# BTS.net
KiCad netlist of a schematic drawn in EAGLE
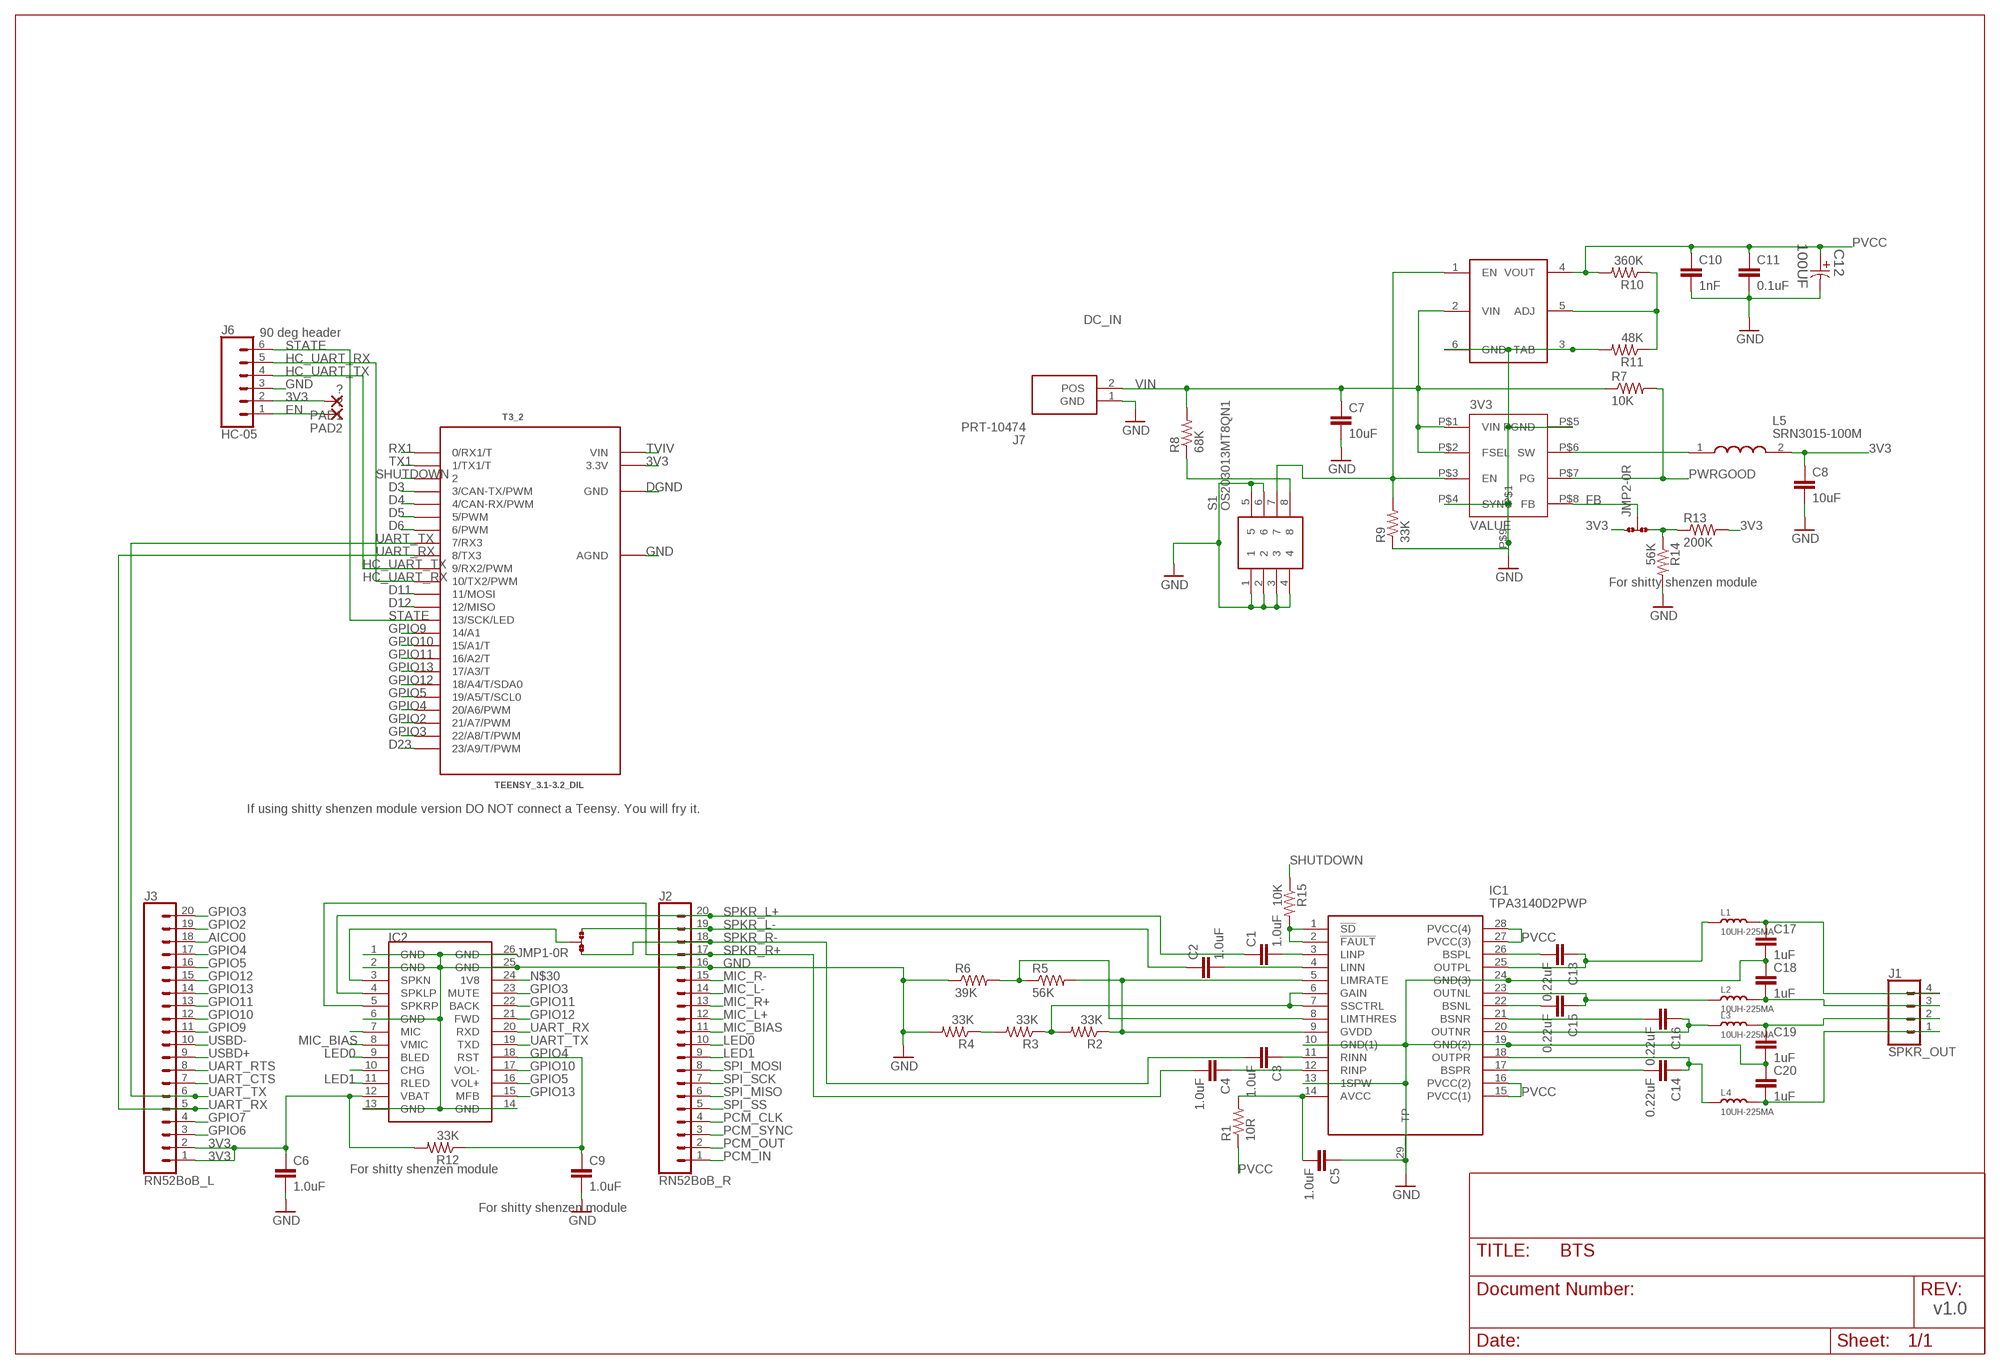
[diagram p0: schematic, sheet 1]

(export (version "E")
  (design (tool "Eeschema 10.0.6"))
  (components
    (comp (ref "3V3")
      (value "ADP2370")
      (footprint "eagle-import:3MM_LFCSP_QFN")
      (libsource (lib "eagle-import") (part "ADP2370"))
    )
    (comp (ref "C1")
      (value "1.0uF")
      (footprint "eagle-import:0603")
      (libsource (lib "eagle-import") (part "1.0UF-0603-16V-10%"))
    )
    (comp (ref "C2")
      (value "1.0uF")
      (footprint "eagle-import:0603")
      (libsource (lib "eagle-import") (part "1.0UF-0603-16V-10%"))
    )
    (comp (ref "C3")
      (value "1.0uF")
      (footprint "eagle-import:0603")
      (libsource (lib "eagle-import") (part "1.0UF-0603-16V-10%"))
    )
    (comp (ref "C4")
      (value "1.0uF")
      (footprint "eagle-import:0603")
      (libsource (lib "eagle-import") (part "1.0UF-0603-16V-10%"))
    )
    (comp (ref "C5")
      (value "1.0uF")
      (footprint "eagle-import:0603")
      (libsource (lib "eagle-import") (part "1.0UF-0603-16V-10%"))
    )
    (comp (ref "C6")
      (value "1.0uF")
      (footprint "eagle-import:0603")
      (libsource (lib "eagle-import") (part "1.0UF-0603-16V-10%"))
    )
    (comp (ref "C7")
      (value "10uF")
      (footprint "eagle-import:C3216")
      (fields (field (name "SPICEPREFIX") "10uF"))
      (libsource (lib "eagle-import") (part "C-EUC3216"))
    )
    (comp (ref "C8")
      (value "10uF")
      (footprint "eagle-import:C3216")
      (libsource (lib "eagle-import") (part "C-EUC3216"))
    )
    (comp (ref "C9")
      (value "1.0uF")
      (footprint "eagle-import:0603")
      (libsource (lib "eagle-import") (part "1.0UF-0603-16V-10%"))
    )
    (comp (ref "C10")
      (value "1nF")
      (footprint "eagle-import:0603")
      (libsource (lib "eagle-import") (part "1.0NF/1000PF-0603-50V-10%"))
    )
    (comp (ref "C11")
      (value "0.1uF")
      (footprint "eagle-import:0603")
      (libsource (lib "eagle-import") (part "0.1UF-0603-25V-(+80/-20%)"))
    )
    (comp (ref "C12")
      (value "100UF")
      (footprint "eagle-import:CAPAE660X610N")
      (fields (field (name "MPN") "EEE-FK1C101P") (field (name "TOLERANCE") "±20 %"))
      (libsource (lib "eagle-import") (part "EEE--CASE-DFK1C101P"))
    )
    (comp (ref "C13")
      (value "0.22uF")
      (footprint "eagle-import:0603")
      (libsource (lib "eagle-import") (part "0.22UF-0603-50V-(-20/+80%)"))
    )
    (comp (ref "C14")
      (value "0.22uF")
      (footprint "eagle-import:0603")
      (libsource (lib "eagle-import") (part "0.22UF-0603-50V-(-20/+80%)"))
    )
    (comp (ref "C15")
      (value "0.22uF")
      (footprint "eagle-import:0603")
      (libsource (lib "eagle-import") (part "0.22UF-0603-50V-(-20/+80%)"))
    )
    (comp (ref "C16")
      (value "0.22uF")
      (footprint "eagle-import:0603")
      (libsource (lib "eagle-import") (part "0.22UF-0603-50V-(-20/+80%)"))
    )
    (comp (ref "C17")
      (value "1uF")
      (footprint "eagle-import:0603")
      (libsource (lib "eagle-import") (part "1.0NF/1000PF-0603-50V-10%"))
    )
    (comp (ref "C18")
      (value "1uF")
      (footprint "eagle-import:0603")
      (libsource (lib "eagle-import") (part "1.0NF/1000PF-0603-50V-10%"))
    )
    (comp (ref "C19")
      (value "1uF")
      (footprint "eagle-import:0603")
      (libsource (lib "eagle-import") (part "1.0NF/1000PF-0603-50V-10%"))
    )
    (comp (ref "C20")
      (value "1uF")
      (footprint "eagle-import:0603")
      (libsource (lib "eagle-import") (part "1.0NF/1000PF-0603-50V-10%"))
    )
    (comp (ref "IC1")
      (value "TPA3140D2PWP")
      (footprint "eagle-import:SOP65P640X120-29N")
      (libsource (lib "eagle-import") (part "TPA3140D2PWP"))
    )
    (comp (ref "IC2")
      (value "BLK-MD-SPK-B")
      (footprint "eagle-import:BLK-MD-SPK-B")
      (libsource (lib "eagle-import") (part "BLK-MD-SPK-B"))
    )
    (comp (ref "J1")
      (value "SPKR_OUT")
      (footprint "eagle-import:SCREWTERMINAL-3.5MM-4")
      (libsource (lib "eagle-import") (part "CONN_04SCREW"))
    )
    (comp (ref "J2")
      (value "RN52BoB_R")
      (footprint "eagle-import:1X20")
      (libsource (lib "eagle-import") (part "CONN_20"))
    )
    (comp (ref "J3")
      (value "RN52BoB_L")
      (footprint "eagle-import:1X20")
      (libsource (lib "eagle-import") (part "CONN_20"))
    )
    (comp (ref "J6")
      (value "HC-05")
      (footprint "eagle-import:1X06")
      (libsource (lib "eagle-import") (part "CONN_06SILK_FEMALE_PTH"))
    )
    (comp (ref "J7")
      (value "PRT-10474")
      (footprint "eagle-import:SHDR2W320P716_1X2_1574X813X158")
      (libsource (lib "eagle-import") (part "PRT-10474"))
    )
    (comp (ref "JMP1")
      (value "0R-JUMPA")
      (footprint "eagle-import:A0R-JMP")
      (libsource (lib "eagle-import") (part "0R-JUMPA"))
    )
    (comp (ref "JMP2")
      (value "0R-JUMPA")
      (footprint "eagle-import:A0R-JMP")
      (libsource (lib "eagle-import") (part "0R-JUMPA"))
    )
    (comp (ref "L1")
      (value "10UH-225MA")
      (footprint "eagle-import:L0806")
      (fields (field (name "MPN") "LQH2MCN100K02L"))
      (libsource (lib "eagle-import") (part "SMD-INDUCTOR-10UH-225MA-10%(0806)"))
    )
    (comp (ref "L2")
      (value "10UH-225MA")
      (footprint "eagle-import:L0806")
      (fields (field (name "MPN") "LQH2MCN100K02L"))
      (libsource (lib "eagle-import") (part "SMD-INDUCTOR-10UH-225MA-10%(0806)"))
    )
    (comp (ref "L3")
      (value "10UH-225MA")
      (footprint "eagle-import:L0806")
      (fields (field (name "MPN") "LQH2MCN100K02L"))
      (libsource (lib "eagle-import") (part "SMD-INDUCTOR-10UH-225MA-10%(0806)"))
    )
    (comp (ref "L4")
      (value "10UH-225MA")
      (footprint "eagle-import:L0806")
      (fields (field (name "MPN") "LQH2MCN100K02L"))
      (libsource (lib "eagle-import") (part "SMD-INDUCTOR-10UH-225MA-10%(0806)"))
    )
    (comp (ref "L5")
      (value "SRN3015-100M")
      (footprint "eagle-import:SRN3015")
      (fields (field (name "RS_PART_NUMBER") "7435071"))
      (libsource (lib "eagle-import") (part "SRN3015-100M"))
    )
    (comp (ref "PAD1")
      (value "?")
      (footprint "eagle-import:SMD1,27-2,54")
      (libsource (lib "eagle-import") (part "SMD2"))
    )
    (comp (ref "PAD2")
      (value "?")
      (footprint "eagle-import:SMD1,27-2,54")
      (libsource (lib "eagle-import") (part "SMD2"))
    )
    (comp (ref "R1")
      (value "10R")
      (footprint "eagle-import:R0603")
      (fields (field (name "RESISTANCE") "10R"))
      (libsource (lib "eagle-import") (part "R-US_R0603"))
    )
    (comp (ref "R2")
      (value "33K")
      (footprint "eagle-import:R0603")
      (fields (field (name "RESISTANCE") "33K"))
      (libsource (lib "eagle-import") (part "R-US_R0603"))
    )
    (comp (ref "R3")
      (value "33K")
      (footprint "eagle-import:R0603")
      (fields (field (name "RESISTANCE") "33K"))
      (libsource (lib "eagle-import") (part "R-US_R0603"))
    )
    (comp (ref "R4")
      (value "33K")
      (footprint "eagle-import:R0603")
      (fields (field (name "RESISTANCE") "33K"))
      (libsource (lib "eagle-import") (part "R-US_R0603"))
    )
    (comp (ref "R5")
      (value "56K")
      (footprint "eagle-import:R0603")
      (fields (field (name "RESISTANCE") "56K"))
      (libsource (lib "eagle-import") (part "R-US_R0603"))
    )
    (comp (ref "R6")
      (value "39K")
      (footprint "eagle-import:R0603")
      (fields (field (name "RESISTANCE") "39K"))
      (libsource (lib "eagle-import") (part "R-US_R0603"))
    )
    (comp (ref "R7")
      (value "10K")
      (footprint "eagle-import:R0603")
      (fields (field (name "RESISTANCE") "10K"))
      (libsource (lib "eagle-import") (part "R-US_R0603"))
    )
    (comp (ref "R8")
      (value "68K")
      (footprint "eagle-import:R0603")
      (fields (field (name "RESISTANCE") "68K"))
      (libsource (lib "eagle-import") (part "R-US_R0603"))
    )
    (comp (ref "R9")
      (value "33K")
      (footprint "eagle-import:R0603")
      (fields (field (name "RESISTANCE") "33K"))
      (libsource (lib "eagle-import") (part "R-US_R0603"))
    )
    (comp (ref "R10")
      (value "360K")
      (footprint "eagle-import:R0603")
      (fields (field (name "RESISTANCE") "10K"))
      (libsource (lib "eagle-import") (part "R-US_R0603"))
    )
    (comp (ref "R11")
      (value "48K")
      (footprint "eagle-import:R0603")
      (fields (field (name "RESISTANCE") "10K"))
      (libsource (lib "eagle-import") (part "R-US_R0603"))
    )
    (comp (ref "R12")
      (value "33K")
      (footprint "eagle-import:R0603")
      (fields (field (name "RESISTANCE") "33K"))
      (libsource (lib "eagle-import") (part "R-US_R0603"))
    )
    (comp (ref "R13")
      (value "200K")
      (footprint "eagle-import:R0603")
      (fields (field (name "RESISTANCE") "10K"))
      (libsource (lib "eagle-import") (part "R-US_R0603"))
    )
    (comp (ref "R14")
      (value "56K")
      (footprint "eagle-import:R0603")
      (fields (field (name "RESISTANCE") "10K"))
      (libsource (lib "eagle-import") (part "R-US_R0603"))
    )
    (comp (ref "R15")
      (value "10K")
      (footprint "eagle-import:R0603")
      (fields (field (name "RESISTANCE") "33K"))
      (libsource (lib "eagle-import") (part "R-US_R0603"))
    )
    (comp (ref "S1")
      (value "OS203013MT8QN1")
      (footprint "eagle-import:OS203013MT8QN1")
      (libsource (lib "eagle-import") (part "OS203013MT8QN1"))
    )
    (comp (ref "T3_2")
      (value "TEENSY_3.1-3.2_DIL")
      (footprint "eagle-import:TEENSY_3.0-3.2&LC_DIL")
      (libsource (lib "eagle-import") (part "TEENSY_3.1-3.2_DIL"))
    )
    (comp (ref "U$2")
      (value "NCP59302")
      (footprint "eagle-import:D2PAK-5")
      (libsource (lib "eagle-import") (part "NCP59302"))
    )
  )
  (nets
    (net (code "1") (name "/3V3") (class "Default")
      (node (ref "C6") (pin "1") (pinfunction "1_1") (pintype "passive"))
      (node (ref "C8") (pin "1") (pinfunction "1_1") (pintype "passive"))
      (node (ref "IC2") (pin "12") (pinfunction "VBAT_12") (pintype "bidirectional"))
      (node (ref "J3") (pin "1") (pinfunction "1_1") (pintype "passive"))
      (node (ref "J3") (pin "2") (pinfunction "2_2") (pintype "passive"))
      (node (ref "J6") (pin "2") (pinfunction "2_2") (pintype "passive"))
      (node (ref "JMP2") (pin "1") (pinfunction "1_1") (pintype "passive"))
      (node (ref "L5") (pin "2") (pinfunction "2_2") (pintype "input"))
      (node (ref "PAD1") (pin "1") (pinfunction "P_1") (pintype "passive"))
      (node (ref "R12") (pin "2") (pinfunction "2_2") (pintype "passive"))
      (node (ref "R13") (pin "2") (pinfunction "2_2") (pintype "passive"))
      (node (ref "T3_2") (pin "3.3V") (pinfunction "3.3V_3.3V") (pintype "power_in"))
    )
    (net (code "2") (name "/AICO0") (class "Default")
      (node (ref "J3") (pin "18") (pinfunction "18_18") (pintype "passive"))
    )
    (net (code "3") (name "/D3") (class "Default")
      (node (ref "T3_2") (pin "3") (pinfunction "3/CAN-TX/PWM_3") (pintype "bidirectional"))
    )
    (net (code "4") (name "/D4") (class "Default")
      (node (ref "T3_2") (pin "4") (pinfunction "4/CAN-RX/PWM_4") (pintype "bidirectional"))
    )
    (net (code "5") (name "/D5") (class "Default")
      (node (ref "T3_2") (pin "5") (pinfunction "5/PWM_5") (pintype "bidirectional"))
    )
    (net (code "6") (name "/D6") (class "Default")
      (node (ref "T3_2") (pin "6") (pinfunction "6/PWM_6") (pintype "bidirectional"))
    )
    (net (code "7") (name "/D11") (class "Default")
      (node (ref "T3_2") (pin "11") (pinfunction "11/MOSI_11") (pintype "bidirectional"))
    )
    (net (code "8") (name "/D12") (class "Default")
      (node (ref "T3_2") (pin "12") (pinfunction "12/MISO_12") (pintype "bidirectional"))
    )
    (net (code "9") (name "/D23") (class "Default")
      (node (ref "T3_2") (pin "23/A9") (pinfunction "23/A9/T/PWM_23/A9") (pintype "bidirectional"))
    )
    (net (code "10") (name "/DGND") (class "Default")
      (node (ref "T3_2") (pin "GND") (pinfunction "GND_GND") (pintype "power_in"))
    )
    (net (code "11") (name "/EN") (class "Default")
      (node (ref "J6") (pin "1") (pinfunction "1_1") (pintype "passive"))
      (node (ref "PAD2") (pin "1") (pinfunction "P_1") (pintype "passive"))
    )
    (net (code "12") (name "/FB") (class "Default")
      (node (ref "3V3") (pin "P$8") (pinfunction "FB_P$8") (pintype "bidirectional"))
      (node (ref "JMP2") (pin "2") (pinfunction "2_2") (pintype "passive"))
    )
    (net (code "13") (name "/GPIO2") (class "Default")
      (node (ref "J3") (pin "19") (pinfunction "19_19") (pintype "passive"))
      (node (ref "T3_2") (pin "21/A7") (pinfunction "21/A7/PWM_21/A7") (pintype "bidirectional"))
    )
    (net (code "14") (name "/GPIO3") (class "Default")
      (node (ref "IC2") (pin "23") (pinfunction "MUTE_23") (pintype "bidirectional"))
      (node (ref "J3") (pin "20") (pinfunction "20_20") (pintype "passive"))
      (node (ref "T3_2") (pin "22/A8") (pinfunction "22/A8/T/PWM_22/A8") (pintype "bidirectional"))
    )
    (net (code "15") (name "/GPIO4") (class "Default")
      (node (ref "C9") (pin "1") (pinfunction "1_1") (pintype "passive"))
      (node (ref "IC2") (pin "18") (pinfunction "RST_18") (pintype "bidirectional"))
      (node (ref "J3") (pin "17") (pinfunction "17_17") (pintype "passive"))
      (node (ref "R12") (pin "1") (pinfunction "1_1") (pintype "passive"))
      (node (ref "T3_2") (pin "20/A6") (pinfunction "20/A6/PWM_20/A6") (pintype "bidirectional"))
    )
    (net (code "16") (name "/GPIO5") (class "Default")
      (node (ref "IC2") (pin "16") (pinfunction "VOL+_16") (pintype "bidirectional"))
      (node (ref "J3") (pin "16") (pinfunction "16_16") (pintype "passive"))
      (node (ref "T3_2") (pin "19/A5") (pinfunction "19/A5/T/SCL0_19/A5") (pintype "bidirectional"))
    )
    (net (code "17") (name "/GPIO6") (class "Default")
      (node (ref "J3") (pin "3") (pinfunction "3_3") (pintype "passive"))
    )
    (net (code "18") (name "/GPIO7") (class "Default")
      (node (ref "J3") (pin "4") (pinfunction "4_4") (pintype "passive"))
    )
    (net (code "19") (name "/GPIO9") (class "Default")
      (node (ref "J3") (pin "11") (pinfunction "11_11") (pintype "passive"))
      (node (ref "T3_2") (pin "14/A0") (pinfunction "14/A1_14/A0") (pintype "bidirectional"))
    )
    (net (code "20") (name "/GPIO10") (class "Default")
      (node (ref "IC2") (pin "17") (pinfunction "VOL-_17") (pintype "bidirectional"))
      (node (ref "J3") (pin "12") (pinfunction "12_12") (pintype "passive"))
      (node (ref "T3_2") (pin "15/A1") (pinfunction "15/A1/T_15/A1") (pintype "bidirectional"))
    )
    (net (code "21") (name "/GPIO11") (class "Default")
      (node (ref "IC2") (pin "22") (pinfunction "BACK_22") (pintype "bidirectional"))
      (node (ref "J3") (pin "13") (pinfunction "13_13") (pintype "passive"))
      (node (ref "T3_2") (pin "16/A2") (pinfunction "16/A2/T_16/A2") (pintype "bidirectional"))
    )
    (net (code "22") (name "/GPIO12") (class "Default")
      (node (ref "IC2") (pin "21") (pinfunction "FWD_21") (pintype "bidirectional"))
      (node (ref "J3") (pin "15") (pinfunction "15_15") (pintype "passive"))
      (node (ref "T3_2") (pin "18/A4") (pinfunction "18/A4/T/SDA0_18/A4") (pintype "bidirectional"))
    )
    (net (code "23") (name "/GPIO13") (class "Default")
      (node (ref "IC2") (pin "15") (pinfunction "MFB_15") (pintype "bidirectional"))
      (node (ref "J3") (pin "14") (pinfunction "14_14") (pintype "passive"))
      (node (ref "T3_2") (pin "17/A3") (pinfunction "17/A3/T_17/A3") (pintype "bidirectional"))
    )
    (net (code "24") (name "/HC_UART_RX") (class "Default")
      (node (ref "J6") (pin "5") (pinfunction "5_5") (pintype "passive"))
      (node (ref "T3_2") (pin "10") (pinfunction "10/TX2/PWM_10") (pintype "bidirectional"))
    )
    (net (code "25") (name "/HC_UART_TX") (class "Default")
      (node (ref "J6") (pin "4") (pinfunction "4_4") (pintype "passive"))
      (node (ref "T3_2") (pin "9") (pinfunction "9/RX2/PWM_9") (pintype "bidirectional"))
    )
    (net (code "26") (name "/LED0") (class "Default")
      (node (ref "IC2") (pin "9") (pinfunction "BLED_9") (pintype "bidirectional"))
      (node (ref "J2") (pin "10") (pinfunction "10_10") (pintype "passive"))
    )
    (net (code "27") (name "/LED1") (class "Default")
      (node (ref "IC2") (pin "11") (pinfunction "RLED_11") (pintype "bidirectional"))
      (node (ref "J2") (pin "9") (pinfunction "9_9") (pintype "passive"))
    )
    (net (code "28") (name "/MIC_BIAS") (class "Default")
      (node (ref "IC2") (pin "8") (pinfunction "VMIC_8") (pintype "bidirectional"))
      (node (ref "J2") (pin "11") (pinfunction "11_11") (pintype "passive"))
    )
    (net (code "29") (name "/MIC_L+") (class "Default")
      (node (ref "J2") (pin "12") (pinfunction "12_12") (pintype "passive"))
    )
    (net (code "30") (name "/MIC_L-") (class "Default")
      (node (ref "J2") (pin "14") (pinfunction "14_14") (pintype "passive"))
    )
    (net (code "31") (name "/MIC_R+") (class "Default")
      (node (ref "J2") (pin "13") (pinfunction "13_13") (pintype "passive"))
    )
    (net (code "32") (name "/MIC_R-") (class "Default")
      (node (ref "J2") (pin "15") (pinfunction "15_15") (pintype "passive"))
    )
    (net (code "33") (name "/N$30") (class "Default")
      (node (ref "IC2") (pin "24") (pinfunction "1V8_24") (pintype "bidirectional"))
    )
    (net (code "34") (name "/PCM_CLK") (class "Default")
      (node (ref "J2") (pin "4") (pinfunction "4_4") (pintype "passive"))
    )
    (net (code "35") (name "/PCM_IN") (class "Default")
      (node (ref "J2") (pin "1") (pinfunction "1_1") (pintype "passive"))
    )
    (net (code "36") (name "/PCM_OUT") (class "Default")
      (node (ref "J2") (pin "2") (pinfunction "2_2") (pintype "passive"))
    )
    (net (code "37") (name "/PCM_SYNC") (class "Default")
      (node (ref "J2") (pin "3") (pinfunction "3_3") (pintype "passive"))
    )
    (net (code "38") (name "/PVCC") (class "Default")
      (node (ref "C10") (pin "1") (pinfunction "1_1") (pintype "passive"))
      (node (ref "C11") (pin "1") (pinfunction "1_1") (pintype "passive"))
      (node (ref "C12") (pin "1") (pinfunction "1_1") (pintype "passive"))
      (node (ref "IC1") (pin "15") (pinfunction "PVCC(1)_15") (pintype "input"))
      (node (ref "IC1") (pin "16") (pinfunction "PVCC(2)_16") (pintype "input"))
      (node (ref "IC1") (pin "27") (pinfunction "PVCC(3)_27") (pintype "input"))
      (node (ref "IC1") (pin "28") (pinfunction "PVCC(4)_28") (pintype "input"))
      (node (ref "R1") (pin "1") (pinfunction "1_1") (pintype "passive"))
      (node (ref "R10") (pin "2") (pinfunction "2_2") (pintype "passive"))
      (node (ref "U$2") (pin "4") (pinfunction "VOUT_4") (pintype "bidirectional"))
    )
    (net (code "39") (name "/PWRGOOD") (class "Default")
      (node (ref "3V3") (pin "P$7") (pinfunction "PG_P$7") (pintype "bidirectional"))
      (node (ref "R7") (pin "2") (pinfunction "2_2") (pintype "passive"))
    )
    (net (code "40") (name "/RX1") (class "Default")
      (node (ref "T3_2") (pin "0") (pinfunction "0/RX1/T_0") (pintype "bidirectional"))
    )
    (net (code "41") (name "/SHUTDOWN") (class "Default")
      (node (ref "R15") (pin "1") (pinfunction "1_1") (pintype "passive"))
      (node (ref "T3_2") (pin "2") (pinfunction "2_2") (pintype "bidirectional"))
    )
    (net (code "42") (name "/SPI_MISO") (class "Default")
      (node (ref "J2") (pin "6") (pinfunction "6_6") (pintype "passive"))
    )
    (net (code "43") (name "/SPI_MOSI") (class "Default")
      (node (ref "J2") (pin "8") (pinfunction "8_8") (pintype "passive"))
    )
    (net (code "44") (name "/SPI_SCK") (class "Default")
      (node (ref "J2") (pin "7") (pinfunction "7_7") (pintype "passive"))
    )
    (net (code "45") (name "/SPI_SS") (class "Default")
      (node (ref "J2") (pin "5") (pinfunction "5_5") (pintype "passive"))
    )
    (net (code "46") (name "/SPKR_L+") (class "Default")
      (node (ref "C1") (pin "1") (pinfunction "1_1") (pintype "passive"))
      (node (ref "IC2") (pin "4") (pinfunction "SPKLP_4") (pintype "bidirectional"))
      (node (ref "J2") (pin "20") (pinfunction "20_20") (pintype "passive"))
    )
    (net (code "47") (name "/SPKR_L-") (class "Default")
      (node (ref "C2") (pin "1") (pinfunction "1_1") (pintype "passive"))
      (node (ref "J2") (pin "19") (pinfunction "19_19") (pintype "passive"))
      (node (ref "JMP1") (pin "3") (pinfunction "3_3") (pintype "passive"))
    )
    (net (code "48") (name "/SPKR_R+") (class "Default")
      (node (ref "C4") (pin "2") (pinfunction "2_2") (pintype "passive"))
      (node (ref "IC2") (pin "5") (pinfunction "SPKRP_5") (pintype "bidirectional"))
      (node (ref "J2") (pin "17") (pinfunction "17_17") (pintype "passive"))
    )
    (net (code "49") (name "/SPKR_R-") (class "Default")
      (node (ref "C3") (pin "2") (pinfunction "2_2") (pintype "passive"))
      (node (ref "J2") (pin "18") (pinfunction "18_18") (pintype "passive"))
      (node (ref "JMP1") (pin "1") (pinfunction "1_1") (pintype "passive"))
    )
    (net (code "50") (name "/STATE") (class "Default")
      (node (ref "J6") (pin "6") (pinfunction "6_6") (pintype "passive"))
      (node (ref "T3_2") (pin "13") (pinfunction "13/SCK/LED_13") (pintype "bidirectional"))
    )
    (net (code "51") (name "/TVIV") (class "Default")
      (node (ref "T3_2") (pin "VIN") (pinfunction "VIN_VIN") (pintype "power_in"))
    )
    (net (code "52") (name "/TX1") (class "Default")
      (node (ref "T3_2") (pin "1") (pinfunction "1/TX1/T_1") (pintype "bidirectional"))
    )
    (net (code "53") (name "/UART_CTS") (class "Default")
      (node (ref "J3") (pin "7") (pinfunction "7_7") (pintype "passive"))
    )
    (net (code "54") (name "/UART_RTS") (class "Default")
      (node (ref "J3") (pin "8") (pinfunction "8_8") (pintype "passive"))
    )
    (net (code "55") (name "/UART_RX") (class "Default")
      (node (ref "IC2") (pin "20") (pinfunction "RXD_20") (pintype "bidirectional"))
      (node (ref "J3") (pin "5") (pinfunction "5_5") (pintype "passive"))
      (node (ref "T3_2") (pin "8") (pinfunction "8/TX3_8") (pintype "bidirectional"))
    )
    (net (code "56") (name "/UART_TX") (class "Default")
      (node (ref "IC2") (pin "19") (pinfunction "TXD_19") (pintype "bidirectional"))
      (node (ref "J3") (pin "6") (pinfunction "6_6") (pintype "passive"))
      (node (ref "T3_2") (pin "7") (pinfunction "7/RX3_7") (pintype "bidirectional"))
    )
    (net (code "57") (name "/USBD+") (class "Default")
      (node (ref "J3") (pin "9") (pinfunction "9_9") (pintype "passive"))
    )
    (net (code "58") (name "/USBD-") (class "Default")
      (node (ref "J3") (pin "10") (pinfunction "10_10") (pintype "passive"))
    )
    (net (code "59") (name "/VIN") (class "Default")
      (node (ref "3V3") (pin "P$1") (pinfunction "VIN_P$1") (pintype "bidirectional"))
      (node (ref "3V3") (pin "P$2") (pinfunction "FSEL_P$2") (pintype "bidirectional"))
      (node (ref "C7") (pin "1") (pinfunction "1_1") (pintype "passive"))
      (node (ref "J7") (pin "2") (pinfunction "POS_2") (pintype "input"))
      (node (ref "R7") (pin "1") (pinfunction "1_1") (pintype "passive"))
      (node (ref "R8") (pin "2") (pinfunction "2_2") (pintype "passive"))
      (node (ref "U$2") (pin "2") (pinfunction "VIN_2") (pintype "bidirectional"))
    )
    (net (code "60") (name "GND") (class "Default")
      (node (ref "3V3") (pin "P$4") (pinfunction "SYNC_P$4") (pintype "bidirectional"))
      (node (ref "3V3") (pin "P$5") (pinfunction "PGND_P$5") (pintype "bidirectional"))
      (node (ref "3V3") (pin "P$9") (pinfunction "P$1_P$9") (pintype "bidirectional"))
      (node (ref "C10") (pin "2") (pinfunction "2_2") (pintype "passive"))
      (node (ref "C11") (pin "2") (pinfunction "2_2") (pintype "passive"))
      (node (ref "C12") (pin "2") (pinfunction "2_2") (pintype "passive"))
      (node (ref "C17") (pin "2") (pinfunction "2_2") (pintype "passive"))
      (node (ref "C18") (pin "1") (pinfunction "1_1") (pintype "passive"))
      (node (ref "C19") (pin "2") (pinfunction "2_2") (pintype "passive"))
      (node (ref "C20") (pin "1") (pinfunction "1_1") (pintype "passive"))
      (node (ref "C5") (pin "1") (pinfunction "1_1") (pintype "passive"))
      (node (ref "C6") (pin "2") (pinfunction "2_2") (pintype "passive"))
      (node (ref "C7") (pin "2") (pinfunction "2_2") (pintype "passive"))
      (node (ref "C8") (pin "2") (pinfunction "2_2") (pintype "passive"))
      (node (ref "C9") (pin "2") (pinfunction "2_2") (pintype "passive"))
      (node (ref "IC1") (pin "10") (pinfunction "GND(1)_10") (pintype "input"))
      (node (ref "IC1") (pin "13") (pinfunction "1SPW_13") (pintype "input"))
      (node (ref "IC1") (pin "19") (pinfunction "GND(2)_19") (pintype "input"))
      (node (ref "IC1") (pin "24") (pinfunction "GND(3)_24") (pintype "input"))
      (node (ref "IC1") (pin "29") (pinfunction "TP_29") (pintype "input"))
      (node (ref "IC2") (pin "1") (pinfunction "GND_1") (pintype "bidirectional"))
      (node (ref "IC2") (pin "13") (pinfunction "GND_13") (pintype "bidirectional"))
      (node (ref "IC2") (pin "14") (pinfunction "GND_14") (pintype "bidirectional"))
      (node (ref "IC2") (pin "2") (pinfunction "GND_2") (pintype "bidirectional"))
      (node (ref "IC2") (pin "25") (pinfunction "GND_25") (pintype "bidirectional"))
      (node (ref "IC2") (pin "26") (pinfunction "GND_26") (pintype "bidirectional"))
      (node (ref "IC2") (pin "6") (pinfunction "GND_6") (pintype "bidirectional"))
      (node (ref "J2") (pin "16") (pinfunction "16_16") (pintype "passive"))
      (node (ref "J6") (pin "3") (pinfunction "3_3") (pintype "passive"))
      (node (ref "J7") (pin "1") (pinfunction "GND_1") (pintype "input"))
      (node (ref "R11") (pin "2") (pinfunction "2_2") (pintype "passive"))
      (node (ref "R14") (pin "2") (pinfunction "2_2") (pintype "passive"))
      (node (ref "R4") (pin "2") (pinfunction "2_2") (pintype "passive"))
      (node (ref "R6") (pin "1") (pinfunction "1_1") (pintype "passive"))
      (node (ref "R9") (pin "1") (pinfunction "1_1") (pintype "passive"))
      (node (ref "S1") (pin "1") (pinfunction "1_1") (pintype "input"))
      (node (ref "S1") (pin "2") (pinfunction "2_2") (pintype "input"))
      (node (ref "S1") (pin "3") (pinfunction "3_3") (pintype "input"))
      (node (ref "S1") (pin "4") (pinfunction "4_4") (pintype "input"))
      (node (ref "S1") (pin "5") (pinfunction "5_5") (pintype "input"))
      (node (ref "S1") (pin "6") (pinfunction "6_6") (pintype "input"))
      (node (ref "T3_2") (pin "AGND") (pinfunction "AGND_AGND") (pintype "power_in"))
      (node (ref "U$2") (pin "3") (pinfunction "TAB_3") (pintype "bidirectional"))
      (node (ref "U$2") (pin "6") (pinfunction "GND_6") (pintype "bidirectional"))
    )
    (net (code "61") (name "Net-(3V3-EN)") (class "Default")
      (node (ref "3V3") (pin "P$3") (pinfunction "EN_P$3") (pintype "bidirectional"))
      (node (ref "R9") (pin "2") (pinfunction "2_2") (pintype "passive"))
      (node (ref "S1") (pin "7") (pinfunction "7_7") (pintype "input"))
      (node (ref "U$2") (pin "1") (pinfunction "EN_1") (pintype "bidirectional"))
    )
    (net (code "62") (name "Net-(3V3-SW)") (class "Default")
      (node (ref "3V3") (pin "P$6") (pinfunction "SW_P$6") (pintype "bidirectional"))
      (node (ref "L5") (pin "1") (pinfunction "1_1") (pintype "input"))
    )
    (net (code "63") (name "Net-(C17-Pad1)") (class "Default")
      (node (ref "C17") (pin "1") (pinfunction "1_1") (pintype "passive"))
      (node (ref "J1") (pin "4") (pinfunction "4_4") (pintype "passive"))
      (node (ref "L1") (pin "2") (pinfunction "2_2") (pintype "passive"))
    )
    (net (code "64") (name "Net-(C18-Pad2)") (class "Default")
      (node (ref "C18") (pin "2") (pinfunction "2_2") (pintype "passive"))
      (node (ref "J1") (pin "3") (pinfunction "3_3") (pintype "passive"))
      (node (ref "L2") (pin "2") (pinfunction "2_2") (pintype "passive"))
    )
    (net (code "65") (name "Net-(C19-Pad1)") (class "Default")
      (node (ref "C19") (pin "1") (pinfunction "1_1") (pintype "passive"))
      (node (ref "J1") (pin "2") (pinfunction "2_2") (pintype "passive"))
      (node (ref "L3") (pin "2") (pinfunction "2_2") (pintype "passive"))
    )
    (net (code "66") (name "Net-(C20-Pad2)") (class "Default")
      (node (ref "C20") (pin "2") (pinfunction "2_2") (pintype "passive"))
      (node (ref "J1") (pin "1") (pinfunction "1_1") (pintype "passive"))
      (node (ref "L4") (pin "2") (pinfunction "2_2") (pintype "passive"))
    )
    (net (code "67") (name "Net-(IC1-AVCC)") (class "Default")
      (node (ref "C5") (pin "2") (pinfunction "2_2") (pintype "passive"))
      (node (ref "IC1") (pin "14") (pinfunction "AVCC_14") (pintype "input"))
      (node (ref "R1") (pin "2") (pinfunction "2_2") (pintype "passive"))
    )
    (net (code "68") (name "Net-(IC1-BSNL)") (class "Default")
      (node (ref "C15") (pin "2") (pinfunction "2_2") (pintype "passive"))
      (node (ref "IC1") (pin "22") (pinfunction "BSNL_22") (pintype "input"))
    )
    (net (code "69") (name "Net-(IC1-BSNR)") (class "Default")
      (node (ref "C16") (pin "2") (pinfunction "2_2") (pintype "passive"))
      (node (ref "IC1") (pin "21") (pinfunction "BSNR_21") (pintype "input"))
    )
    (net (code "70") (name "Net-(IC1-BSPL)") (class "Default")
      (node (ref "C13") (pin "2") (pinfunction "2_2") (pintype "passive"))
      (node (ref "IC1") (pin "26") (pinfunction "BSPL_26") (pintype "input"))
    )
    (net (code "71") (name "Net-(IC1-BSPR)") (class "Default")
      (node (ref "C14") (pin "2") (pinfunction "2_2") (pintype "passive"))
      (node (ref "IC1") (pin "17") (pinfunction "BSPR_17") (pintype "input"))
    )
    (net (code "72") (name "Net-(IC1-GAIN)") (class "Default")
      (node (ref "IC1") (pin "6") (pinfunction "GAIN_6") (pintype "input"))
      (node (ref "IC1") (pin "7") (pinfunction "SSCTRL_7") (pintype "input"))
      (node (ref "R2") (pin "2") (pinfunction "2_2") (pintype "passive"))
      (node (ref "R3") (pin "1") (pinfunction "1_1") (pintype "passive"))
    )
    (net (code "73") (name "Net-(IC1-GVDD)") (class "Default")
      (node (ref "IC1") (pin "5") (pinfunction "LIMRATE_5") (pintype "input"))
      (node (ref "IC1") (pin "9") (pinfunction "GVDD_9") (pintype "input"))
      (node (ref "R2") (pin "1") (pinfunction "1_1") (pintype "passive"))
      (node (ref "R5") (pin "2") (pinfunction "2_2") (pintype "passive"))
    )
    (net (code "74") (name "Net-(IC1-LIMTHRES)") (class "Default")
      (node (ref "IC1") (pin "8") (pinfunction "LIMTHRES_8") (pintype "input"))
      (node (ref "R5") (pin "1") (pinfunction "1_1") (pintype "passive"))
      (node (ref "R6") (pin "2") (pinfunction "2_2") (pintype "passive"))
    )
    (net (code "75") (name "Net-(IC1-LINN)") (class "Default")
      (node (ref "C2") (pin "2") (pinfunction "2_2") (pintype "passive"))
      (node (ref "IC1") (pin "4") (pinfunction "LINN_4") (pintype "input"))
    )
    (net (code "76") (name "Net-(IC1-LINP)") (class "Default")
      (node (ref "C1") (pin "2") (pinfunction "2_2") (pintype "passive"))
      (node (ref "IC1") (pin "3") (pinfunction "LINP_3") (pintype "input"))
    )
    (net (code "77") (name "Net-(IC1-OUTNL)") (class "Default")
      (node (ref "C15") (pin "1") (pinfunction "1_1") (pintype "passive"))
      (node (ref "IC1") (pin "23") (pinfunction "OUTNL_23") (pintype "input"))
      (node (ref "L2") (pin "1") (pinfunction "1_1") (pintype "passive"))
    )
    (net (code "78") (name "Net-(IC1-OUTNR)") (class "Default")
      (node (ref "C16") (pin "1") (pinfunction "1_1") (pintype "passive"))
      (node (ref "IC1") (pin "20") (pinfunction "OUTNR_20") (pintype "input"))
      (node (ref "L3") (pin "1") (pinfunction "1_1") (pintype "passive"))
    )
    (net (code "79") (name "Net-(IC1-OUTPL)") (class "Default")
      (node (ref "C13") (pin "1") (pinfunction "1_1") (pintype "passive"))
      (node (ref "IC1") (pin "25") (pinfunction "OUTPL_25") (pintype "input"))
      (node (ref "L1") (pin "1") (pinfunction "1_1") (pintype "passive"))
    )
    (net (code "80") (name "Net-(IC1-OUTPR)") (class "Default")
      (node (ref "C14") (pin "1") (pinfunction "1_1") (pintype "passive"))
      (node (ref "IC1") (pin "18") (pinfunction "OUTPR_18") (pintype "input"))
      (node (ref "L4") (pin "1") (pinfunction "1_1") (pintype "passive"))
    )
    (net (code "81") (name "Net-(IC1-RINN)") (class "Default")
      (node (ref "C3") (pin "1") (pinfunction "1_1") (pintype "passive"))
      (node (ref "IC1") (pin "11") (pinfunction "RINN_11") (pintype "input"))
    )
    (net (code "82") (name "Net-(IC1-RINP)") (class "Default")
      (node (ref "C4") (pin "1") (pinfunction "1_1") (pintype "passive"))
      (node (ref "IC1") (pin "12") (pinfunction "RINP_12") (pintype "input"))
    )
    (net (code "83") (name "Net-(IC1-~{FAULT})") (class "Default")
      (node (ref "IC1") (pin "1") (pinfunction "~{SD}_1") (pintype "input"))
      (node (ref "IC1") (pin "2") (pinfunction "~{FAULT}_2") (pintype "input"))
      (node (ref "R15") (pin "2") (pinfunction "2_2") (pintype "passive"))
    )
    (net (code "84") (name "Net-(IC2-SPKN)") (class "Default")
      (node (ref "IC2") (pin "3") (pinfunction "SPKN_3") (pintype "bidirectional"))
      (node (ref "JMP1") (pin "2") (pinfunction "2_2") (pintype "passive"))
    )
    (net (code "85") (name "Net-(JMP2-Pad3)") (class "Default")
      (node (ref "JMP2") (pin "3") (pinfunction "3_3") (pintype "passive"))
      (node (ref "R13") (pin "1") (pinfunction "1_1") (pintype "passive"))
      (node (ref "R14") (pin "1") (pinfunction "1_1") (pintype "passive"))
    )
    (net (code "86") (name "Net-(R3-Pad2)") (class "Default")
      (node (ref "R3") (pin "2") (pinfunction "2_2") (pintype "passive"))
      (node (ref "R4") (pin "1") (pinfunction "1_1") (pintype "passive"))
    )
    (net (code "87") (name "Net-(R8-Pad1)") (class "Default")
      (node (ref "R8") (pin "1") (pinfunction "1_1") (pintype "passive"))
      (node (ref "S1") (pin "8") (pinfunction "8_8") (pintype "input"))
    )
    (net (code "88") (name "Net-(U$2-ADJ)") (class "Default")
      (node (ref "R10") (pin "1") (pinfunction "1_1") (pintype "passive"))
      (node (ref "R11") (pin "1") (pinfunction "1_1") (pintype "passive"))
      (node (ref "U$2") (pin "5") (pinfunction "ADJ_5") (pintype "bidirectional"))
    )
    (net (code "89") (name "unconnected-(IC2-CHG-Pad10)") (class "Default")
      (node (ref "IC2") (pin "10") (pinfunction "CHG_10") (pintype "bidirectional"))
    )
    (net (code "90") (name "unconnected-(IC2-MIC-Pad7)") (class "Default")
      (node (ref "IC2") (pin "7") (pinfunction "MIC_7") (pintype "bidirectional"))
    )
  )
)
